# batt.net
KiCad netlist of a schematic drawn in EAGLE
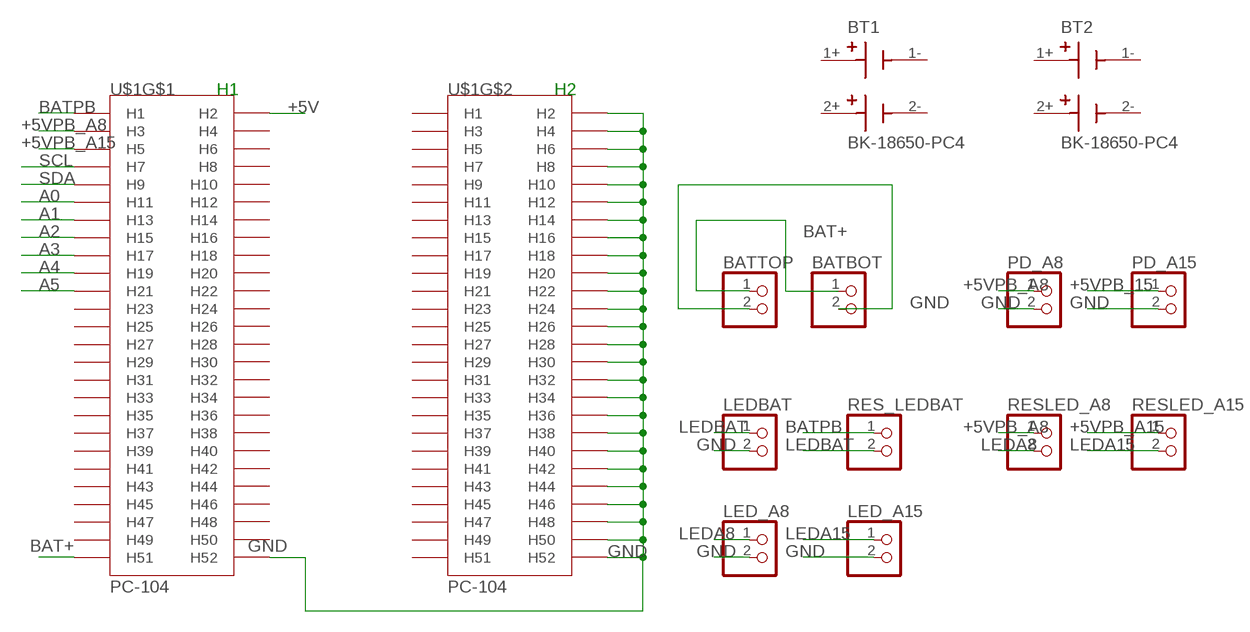
[diagram p0: schematic, sheet 1]

(export (version "E")
  (design (tool "Eeschema 10.0.6"))
  (components
    (comp (ref "BATBOT")
      (value "PINHD-1X2")
      (footprint "eagle-import:1X02")
      (libsource (lib "eagle-import") (part "PINHD-1X2"))
    )
    (comp (ref "BATTOP")
      (value "PINHD-1X2")
      (footprint "eagle-import:1X02")
      (libsource (lib "eagle-import") (part "PINHD-1X2"))
    )
    (comp (ref "BT1")
      (value "BK-18650-PC4")
      (footprint "eagle-import:BAT_BK-18650-PC4")
      (fields (field (name "MF") "MPD"))
      (libsource (lib "eagle-import") (part "BK-18650-PC4"))
    )
    (comp (ref "BT2")
      (value "BK-18650-PC4")
      (footprint "eagle-import:BAT_BK-18650-PC4")
      (fields (field (name "MF") "MPD"))
      (libsource (lib "eagle-import") (part "BK-18650-PC4"))
    )
    (comp (ref "LEDBAT")
      (value "PINHD-1X2")
      (footprint "eagle-import:1X02")
      (libsource (lib "eagle-import") (part "PINHD-1X2"))
    )
    (comp (ref "LED_A8")
      (value "PINHD-1X2")
      (footprint "eagle-import:1X02")
      (libsource (lib "eagle-import") (part "PINHD-1X2"))
    )
    (comp (ref "LED_A15")
      (value "PINHD-1X2")
      (footprint "eagle-import:1X02")
      (libsource (lib "eagle-import") (part "PINHD-1X2"))
    )
    (comp (ref "PD_A8")
      (value "PINHD-1X2")
      (footprint "eagle-import:1X02")
      (libsource (lib "eagle-import") (part "PINHD-1X2"))
    )
    (comp (ref "PD_A15")
      (value "PINHD-1X2")
      (footprint "eagle-import:1X02")
      (libsource (lib "eagle-import") (part "PINHD-1X2"))
    )
    (comp (ref "RESLED_A8")
      (value "PINHD-1X2")
      (footprint "eagle-import:1X02")
      (libsource (lib "eagle-import") (part "PINHD-1X2"))
    )
    (comp (ref "RESLED_A15")
      (value "PINHD-1X2")
      (footprint "eagle-import:1X02")
      (libsource (lib "eagle-import") (part "PINHD-1X2"))
    )
    (comp (ref "RES_LEDBAT")
      (value "PINHD-1X2")
      (footprint "eagle-import:1X02")
      (libsource (lib "eagle-import") (part "PINHD-1X2"))
    )
    (comp (ref "U$1")
      (value "PC-104")
      (footprint "eagle-import:PC-104")
      (libsource (lib "eagle-import") (part "PC-104"))
    )
  )
  (nets
    (net (code "1") (name "/+5V") (class "Default")
      (node (ref "U$1") (pin "P$2") (pinfunction "H2_P$2") (pintype "bidirectional"))
    )
    (net (code "2") (name "/+5VPB_15") (class "Default")
      (node (ref "PD_A15") (pin "1") (pinfunction "1_1") (pintype "passive"))
    )
    (net (code "3") (name "/+5VPB_A8") (class "Default")
      (node (ref "PD_A8") (pin "1") (pinfunction "1_1") (pintype "passive"))
      (node (ref "RESLED_A8") (pin "1") (pinfunction "1_1") (pintype "passive"))
      (node (ref "U$1") (pin "P$3") (pinfunction "H3_P$3") (pintype "bidirectional"))
    )
    (net (code "4") (name "/+5VPB_A15") (class "Default")
      (node (ref "RESLED_A15") (pin "1") (pinfunction "1_1") (pintype "passive"))
      (node (ref "U$1") (pin "P$5") (pinfunction "H5_P$5") (pintype "bidirectional"))
    )
    (net (code "5") (name "/A0") (class "Default")
      (node (ref "U$1") (pin "P$11") (pinfunction "H11_P$11") (pintype "bidirectional"))
    )
    (net (code "6") (name "/A1") (class "Default")
      (node (ref "U$1") (pin "P$13") (pinfunction "H13_P$13") (pintype "bidirectional"))
    )
    (net (code "7") (name "/A2") (class "Default")
      (node (ref "U$1") (pin "P$15") (pinfunction "H15_P$15") (pintype "bidirectional"))
    )
    (net (code "8") (name "/A3") (class "Default")
      (node (ref "U$1") (pin "P$17") (pinfunction "H17_P$17") (pintype "bidirectional"))
    )
    (net (code "9") (name "/A4") (class "Default")
      (node (ref "U$1") (pin "P$19") (pinfunction "H19_P$19") (pintype "bidirectional"))
    )
    (net (code "10") (name "/A5") (class "Default")
      (node (ref "U$1") (pin "P$21") (pinfunction "H21_P$21") (pintype "bidirectional"))
    )
    (net (code "11") (name "/BAT+") (class "Default")
      (node (ref "BATBOT") (pin "1") (pinfunction "1_1") (pintype "passive"))
      (node (ref "BATTOP") (pin "1") (pinfunction "1_1") (pintype "passive"))
      (node (ref "U$1") (pin "P$51") (pinfunction "H51_P$51") (pintype "bidirectional"))
    )
    (net (code "12") (name "/BATPB") (class "Default")
      (node (ref "RES_LEDBAT") (pin "1") (pinfunction "1_1") (pintype "passive"))
      (node (ref "U$1") (pin "P$1") (pinfunction "H1_P$1") (pintype "bidirectional"))
    )
    (net (code "13") (name "/GND") (class "Default")
      (node (ref "BATBOT") (pin "2") (pinfunction "2_2") (pintype "passive"))
      (node (ref "BATTOP") (pin "2") (pinfunction "2_2") (pintype "passive"))
      (node (ref "LEDBAT") (pin "2") (pinfunction "2_2") (pintype "passive"))
      (node (ref "LED_A15") (pin "2") (pinfunction "2_2") (pintype "passive"))
      (node (ref "LED_A8") (pin "2") (pinfunction "2_2") (pintype "passive"))
      (node (ref "PD_A15") (pin "2") (pinfunction "2_2") (pintype "passive"))
      (node (ref "PD_A8") (pin "2") (pinfunction "2_2") (pintype "passive"))
      (node (ref "U$1") (pin "P$100") (pinfunction "H48_P$100") (pintype "bidirectional"))
      (node (ref "U$1") (pin "P$102") (pinfunction "H50_P$102") (pintype "bidirectional"))
      (node (ref "U$1") (pin "P$104") (pinfunction "H52_P$104") (pintype "bidirectional"))
      (node (ref "U$1") (pin "P$52") (pinfunction "H52_P$52") (pintype "bidirectional"))
      (node (ref "U$1") (pin "P$54") (pinfunction "H2_P$54") (pintype "bidirectional"))
      (node (ref "U$1") (pin "P$56") (pinfunction "H4_P$56") (pintype "bidirectional"))
      (node (ref "U$1") (pin "P$58") (pinfunction "H6_P$58") (pintype "bidirectional"))
      (node (ref "U$1") (pin "P$60") (pinfunction "H8_P$60") (pintype "bidirectional"))
      (node (ref "U$1") (pin "P$62") (pinfunction "H10_P$62") (pintype "bidirectional"))
      (node (ref "U$1") (pin "P$64") (pinfunction "H12_P$64") (pintype "bidirectional"))
      (node (ref "U$1") (pin "P$66") (pinfunction "H14_P$66") (pintype "bidirectional"))
      (node (ref "U$1") (pin "P$68") (pinfunction "H16_P$68") (pintype "bidirectional"))
      (node (ref "U$1") (pin "P$70") (pinfunction "H18_P$70") (pintype "bidirectional"))
      (node (ref "U$1") (pin "P$72") (pinfunction "H20_P$72") (pintype "bidirectional"))
      (node (ref "U$1") (pin "P$74") (pinfunction "H22_P$74") (pintype "bidirectional"))
      (node (ref "U$1") (pin "P$76") (pinfunction "H24_P$76") (pintype "bidirectional"))
      (node (ref "U$1") (pin "P$78") (pinfunction "H26_P$78") (pintype "bidirectional"))
      (node (ref "U$1") (pin "P$80") (pinfunction "H28_P$80") (pintype "bidirectional"))
      (node (ref "U$1") (pin "P$82") (pinfunction "H30_P$82") (pintype "bidirectional"))
      (node (ref "U$1") (pin "P$84") (pinfunction "H32_P$84") (pintype "bidirectional"))
      (node (ref "U$1") (pin "P$86") (pinfunction "H34_P$86") (pintype "bidirectional"))
      (node (ref "U$1") (pin "P$88") (pinfunction "H36_P$88") (pintype "bidirectional"))
      (node (ref "U$1") (pin "P$90") (pinfunction "H38_P$90") (pintype "bidirectional"))
      (node (ref "U$1") (pin "P$92") (pinfunction "H40_P$92") (pintype "bidirectional"))
      (node (ref "U$1") (pin "P$94") (pinfunction "H42_P$94") (pintype "bidirectional"))
      (node (ref "U$1") (pin "P$96") (pinfunction "H44_P$96") (pintype "bidirectional"))
      (node (ref "U$1") (pin "P$98") (pinfunction "H46_P$98") (pintype "bidirectional"))
    )
    (net (code "14") (name "/LEDA8") (class "Default")
      (node (ref "LED_A8") (pin "1") (pinfunction "1_1") (pintype "passive"))
      (node (ref "RESLED_A8") (pin "2") (pinfunction "2_2") (pintype "passive"))
    )
    (net (code "15") (name "/LEDA15") (class "Default")
      (node (ref "LED_A15") (pin "1") (pinfunction "1_1") (pintype "passive"))
      (node (ref "RESLED_A15") (pin "2") (pinfunction "2_2") (pintype "passive"))
    )
    (net (code "16") (name "/LEDBAT") (class "Default")
      (node (ref "LEDBAT") (pin "1") (pinfunction "1_1") (pintype "passive"))
      (node (ref "RES_LEDBAT") (pin "2") (pinfunction "2_2") (pintype "passive"))
    )
    (net (code "17") (name "/SCL") (class "Default")
      (node (ref "U$1") (pin "P$7") (pinfunction "H7_P$7") (pintype "bidirectional"))
    )
    (net (code "18") (name "/SDA") (class "Default")
      (node (ref "U$1") (pin "P$9") (pinfunction "H9_P$9") (pintype "bidirectional"))
    )
    (net (code "19") (name "unconnected-(BT1-Pad1+)") (class "Default")
      (node (ref "BT1") (pin "1+") (pinfunction "1+_1+") (pintype "passive"))
    )
    (net (code "20") (name "unconnected-(BT1-Pad1-)") (class "Default")
      (node (ref "BT1") (pin "1-") (pinfunction "1-_1-") (pintype "passive"))
    )
    (net (code "21") (name "unconnected-(BT1-Pad2+)") (class "Default")
      (node (ref "BT1") (pin "2+") (pinfunction "2+_2+") (pintype "passive"))
    )
    (net (code "22") (name "unconnected-(BT1-Pad2-)") (class "Default")
      (node (ref "BT1") (pin "2-") (pinfunction "2-_2-") (pintype "passive"))
    )
    (net (code "23") (name "unconnected-(BT2-Pad1+)") (class "Default")
      (node (ref "BT2") (pin "1+") (pinfunction "1+_1+") (pintype "passive"))
    )
    (net (code "24") (name "unconnected-(BT2-Pad1-)") (class "Default")
      (node (ref "BT2") (pin "1-") (pinfunction "1-_1-") (pintype "passive"))
    )
    (net (code "25") (name "unconnected-(BT2-Pad2+)") (class "Default")
      (node (ref "BT2") (pin "2+") (pinfunction "2+_2+") (pintype "passive"))
    )
    (net (code "26") (name "unconnected-(BT2-Pad2-)") (class "Default")
      (node (ref "BT2") (pin "2-") (pinfunction "2-_2-") (pintype "passive"))
    )
    (net (code "27") (name "unconnected-(U$1A-H4-PadP$4)") (class "Default")
      (node (ref "U$1") (pin "P$4") (pinfunction "H4_P$4") (pintype "bidirectional"))
    )
    (net (code "28") (name "unconnected-(U$1A-H6-PadP$6)") (class "Default")
      (node (ref "U$1") (pin "P$6") (pinfunction "H6_P$6") (pintype "bidirectional"))
    )
    (net (code "29") (name "unconnected-(U$1A-H8-PadP$8)") (class "Default")
      (node (ref "U$1") (pin "P$8") (pinfunction "H8_P$8") (pintype "bidirectional"))
    )
    (net (code "30") (name "unconnected-(U$1A-H10-PadP$10)") (class "Default")
      (node (ref "U$1") (pin "P$10") (pinfunction "H10_P$10") (pintype "bidirectional"))
    )
    (net (code "31") (name "unconnected-(U$1A-H12-PadP$12)") (class "Default")
      (node (ref "U$1") (pin "P$12") (pinfunction "H12_P$12") (pintype "bidirectional"))
    )
    (net (code "32") (name "unconnected-(U$1A-H14-PadP$14)") (class "Default")
      (node (ref "U$1") (pin "P$14") (pinfunction "H14_P$14") (pintype "bidirectional"))
    )
    (net (code "33") (name "unconnected-(U$1A-H16-PadP$16)") (class "Default")
      (node (ref "U$1") (pin "P$16") (pinfunction "H16_P$16") (pintype "bidirectional"))
    )
    (net (code "34") (name "unconnected-(U$1A-H18-PadP$18)") (class "Default")
      (node (ref "U$1") (pin "P$18") (pinfunction "H18_P$18") (pintype "bidirectional"))
    )
    (net (code "35") (name "unconnected-(U$1A-H20-PadP$20)") (class "Default")
      (node (ref "U$1") (pin "P$20") (pinfunction "H20_P$20") (pintype "bidirectional"))
    )
    (net (code "36") (name "unconnected-(U$1A-H22-PadP$22)") (class "Default")
      (node (ref "U$1") (pin "P$22") (pinfunction "H22_P$22") (pintype "bidirectional"))
    )
    (net (code "37") (name "unconnected-(U$1A-H23-PadP$23)") (class "Default")
      (node (ref "U$1") (pin "P$23") (pinfunction "H23_P$23") (pintype "bidirectional"))
    )
    (net (code "38") (name "unconnected-(U$1A-H24-PadP$24)") (class "Default")
      (node (ref "U$1") (pin "P$24") (pinfunction "H24_P$24") (pintype "bidirectional"))
    )
    (net (code "39") (name "unconnected-(U$1A-H25-PadP$25)") (class "Default")
      (node (ref "U$1") (pin "P$25") (pinfunction "H25_P$25") (pintype "bidirectional"))
    )
    (net (code "40") (name "unconnected-(U$1A-H26-PadP$26)") (class "Default")
      (node (ref "U$1") (pin "P$26") (pinfunction "H26_P$26") (pintype "bidirectional"))
    )
    (net (code "41") (name "unconnected-(U$1A-H27-PadP$27)") (class "Default")
      (node (ref "U$1") (pin "P$27") (pinfunction "H27_P$27") (pintype "bidirectional"))
    )
    (net (code "42") (name "unconnected-(U$1A-H28-PadP$28)") (class "Default")
      (node (ref "U$1") (pin "P$28") (pinfunction "H28_P$28") (pintype "bidirectional"))
    )
    (net (code "43") (name "unconnected-(U$1A-H29-PadP$29)") (class "Default")
      (node (ref "U$1") (pin "P$29") (pinfunction "H29_P$29") (pintype "bidirectional"))
    )
    (net (code "44") (name "unconnected-(U$1A-H30-PadP$30)") (class "Default")
      (node (ref "U$1") (pin "P$30") (pinfunction "H30_P$30") (pintype "bidirectional"))
    )
    (net (code "45") (name "unconnected-(U$1A-H31-PadP$31)") (class "Default")
      (node (ref "U$1") (pin "P$31") (pinfunction "H31_P$31") (pintype "bidirectional"))
    )
    (net (code "46") (name "unconnected-(U$1A-H32-PadP$32)") (class "Default")
      (node (ref "U$1") (pin "P$32") (pinfunction "H32_P$32") (pintype "bidirectional"))
    )
    (net (code "47") (name "unconnected-(U$1A-H33-PadP$33)") (class "Default")
      (node (ref "U$1") (pin "P$33") (pinfunction "H33_P$33") (pintype "bidirectional"))
    )
    (net (code "48") (name "unconnected-(U$1A-H34-PadP$34)") (class "Default")
      (node (ref "U$1") (pin "P$34") (pinfunction "H34_P$34") (pintype "bidirectional"))
    )
    (net (code "49") (name "unconnected-(U$1A-H35-PadP$35)") (class "Default")
      (node (ref "U$1") (pin "P$35") (pinfunction "H35_P$35") (pintype "bidirectional"))
    )
    (net (code "50") (name "unconnected-(U$1A-H36-PadP$36)") (class "Default")
      (node (ref "U$1") (pin "P$36") (pinfunction "H36_P$36") (pintype "bidirectional"))
    )
    (net (code "51") (name "unconnected-(U$1A-H37-PadP$37)") (class "Default")
      (node (ref "U$1") (pin "P$37") (pinfunction "H37_P$37") (pintype "bidirectional"))
    )
    (net (code "52") (name "unconnected-(U$1A-H38-PadP$38)") (class "Default")
      (node (ref "U$1") (pin "P$38") (pinfunction "H38_P$38") (pintype "bidirectional"))
    )
    (net (code "53") (name "unconnected-(U$1A-H39-PadP$39)") (class "Default")
      (node (ref "U$1") (pin "P$39") (pinfunction "H39_P$39") (pintype "bidirectional"))
    )
    (net (code "54") (name "unconnected-(U$1A-H40-PadP$40)") (class "Default")
      (node (ref "U$1") (pin "P$40") (pinfunction "H40_P$40") (pintype "bidirectional"))
    )
    (net (code "55") (name "unconnected-(U$1A-H41-PadP$41)") (class "Default")
      (node (ref "U$1") (pin "P$41") (pinfunction "H41_P$41") (pintype "bidirectional"))
    )
    (net (code "56") (name "unconnected-(U$1A-H42-PadP$42)") (class "Default")
      (node (ref "U$1") (pin "P$42") (pinfunction "H42_P$42") (pintype "bidirectional"))
    )
    (net (code "57") (name "unconnected-(U$1A-H43-PadP$43)") (class "Default")
      (node (ref "U$1") (pin "P$43") (pinfunction "H43_P$43") (pintype "bidirectional"))
    )
    (net (code "58") (name "unconnected-(U$1A-H44-PadP$44)") (class "Default")
      (node (ref "U$1") (pin "P$44") (pinfunction "H44_P$44") (pintype "bidirectional"))
    )
    (net (code "59") (name "unconnected-(U$1A-H45-PadP$45)") (class "Default")
      (node (ref "U$1") (pin "P$45") (pinfunction "H45_P$45") (pintype "bidirectional"))
    )
    (net (code "60") (name "unconnected-(U$1A-H46-PadP$46)") (class "Default")
      (node (ref "U$1") (pin "P$46") (pinfunction "H46_P$46") (pintype "bidirectional"))
    )
    (net (code "61") (name "unconnected-(U$1A-H47-PadP$47)") (class "Default")
      (node (ref "U$1") (pin "P$47") (pinfunction "H47_P$47") (pintype "bidirectional"))
    )
    (net (code "62") (name "unconnected-(U$1A-H48-PadP$48)") (class "Default")
      (node (ref "U$1") (pin "P$48") (pinfunction "H48_P$48") (pintype "bidirectional"))
    )
    (net (code "63") (name "unconnected-(U$1A-H49-PadP$49)") (class "Default")
      (node (ref "U$1") (pin "P$49") (pinfunction "H49_P$49") (pintype "bidirectional"))
    )
    (net (code "64") (name "unconnected-(U$1A-H50-PadP$50)") (class "Default")
      (node (ref "U$1") (pin "P$50") (pinfunction "H50_P$50") (pintype "bidirectional"))
    )
    (net (code "65") (name "unconnected-(U$1B-H1-PadP$53)") (class "Default")
      (node (ref "U$1") (pin "P$53") (pinfunction "H1_P$53") (pintype "bidirectional"))
    )
    (net (code "66") (name "unconnected-(U$1B-H3-PadP$55)") (class "Default")
      (node (ref "U$1") (pin "P$55") (pinfunction "H3_P$55") (pintype "bidirectional"))
    )
    (net (code "67") (name "unconnected-(U$1B-H5-PadP$57)") (class "Default")
      (node (ref "U$1") (pin "P$57") (pinfunction "H5_P$57") (pintype "bidirectional"))
    )
    (net (code "68") (name "unconnected-(U$1B-H7-PadP$59)") (class "Default")
      (node (ref "U$1") (pin "P$59") (pinfunction "H7_P$59") (pintype "bidirectional"))
    )
    (net (code "69") (name "unconnected-(U$1B-H9-PadP$61)") (class "Default")
      (node (ref "U$1") (pin "P$61") (pinfunction "H9_P$61") (pintype "bidirectional"))
    )
    (net (code "70") (name "unconnected-(U$1B-H11-PadP$63)") (class "Default")
      (node (ref "U$1") (pin "P$63") (pinfunction "H11_P$63") (pintype "bidirectional"))
    )
    (net (code "71") (name "unconnected-(U$1B-H13-PadP$65)") (class "Default")
      (node (ref "U$1") (pin "P$65") (pinfunction "H13_P$65") (pintype "bidirectional"))
    )
    (net (code "72") (name "unconnected-(U$1B-H15-PadP$67)") (class "Default")
      (node (ref "U$1") (pin "P$67") (pinfunction "H15_P$67") (pintype "bidirectional"))
    )
    (net (code "73") (name "unconnected-(U$1B-H17-PadP$69)") (class "Default")
      (node (ref "U$1") (pin "P$69") (pinfunction "H17_P$69") (pintype "bidirectional"))
    )
    (net (code "74") (name "unconnected-(U$1B-H19-PadP$71)") (class "Default")
      (node (ref "U$1") (pin "P$71") (pinfunction "H19_P$71") (pintype "bidirectional"))
    )
    (net (code "75") (name "unconnected-(U$1B-H21-PadP$73)") (class "Default")
      (node (ref "U$1") (pin "P$73") (pinfunction "H21_P$73") (pintype "bidirectional"))
    )
    (net (code "76") (name "unconnected-(U$1B-H23-PadP$75)") (class "Default")
      (node (ref "U$1") (pin "P$75") (pinfunction "H23_P$75") (pintype "bidirectional"))
    )
    (net (code "77") (name "unconnected-(U$1B-H25-PadP$77)") (class "Default")
      (node (ref "U$1") (pin "P$77") (pinfunction "H25_P$77") (pintype "bidirectional"))
    )
    (net (code "78") (name "unconnected-(U$1B-H27-PadP$79)") (class "Default")
      (node (ref "U$1") (pin "P$79") (pinfunction "H27_P$79") (pintype "bidirectional"))
    )
    (net (code "79") (name "unconnected-(U$1B-H29-PadP$81)") (class "Default")
      (node (ref "U$1") (pin "P$81") (pinfunction "H29_P$81") (pintype "bidirectional"))
    )
    (net (code "80") (name "unconnected-(U$1B-H31-PadP$83)") (class "Default")
      (node (ref "U$1") (pin "P$83") (pinfunction "H31_P$83") (pintype "bidirectional"))
    )
    (net (code "81") (name "unconnected-(U$1B-H33-PadP$85)") (class "Default")
      (node (ref "U$1") (pin "P$85") (pinfunction "H33_P$85") (pintype "bidirectional"))
    )
    (net (code "82") (name "unconnected-(U$1B-H35-PadP$87)") (class "Default")
      (node (ref "U$1") (pin "P$87") (pinfunction "H35_P$87") (pintype "bidirectional"))
    )
    (net (code "83") (name "unconnected-(U$1B-H37-PadP$89)") (class "Default")
      (node (ref "U$1") (pin "P$89") (pinfunction "H37_P$89") (pintype "bidirectional"))
    )
    (net (code "84") (name "unconnected-(U$1B-H39-PadP$91)") (class "Default")
      (node (ref "U$1") (pin "P$91") (pinfunction "H39_P$91") (pintype "bidirectional"))
    )
    (net (code "85") (name "unconnected-(U$1B-H41-PadP$93)") (class "Default")
      (node (ref "U$1") (pin "P$93") (pinfunction "H41_P$93") (pintype "bidirectional"))
    )
    (net (code "86") (name "unconnected-(U$1B-H43-PadP$95)") (class "Default")
      (node (ref "U$1") (pin "P$95") (pinfunction "H43_P$95") (pintype "bidirectional"))
    )
    (net (code "87") (name "unconnected-(U$1B-H45-PadP$97)") (class "Default")
      (node (ref "U$1") (pin "P$97") (pinfunction "H45_P$97") (pintype "bidirectional"))
    )
    (net (code "88") (name "unconnected-(U$1B-H47-PadP$99)") (class "Default")
      (node (ref "U$1") (pin "P$99") (pinfunction "H47_P$99") (pintype "bidirectional"))
    )
    (net (code "89") (name "unconnected-(U$1B-H49-PadP$101)") (class "Default")
      (node (ref "U$1") (pin "P$101") (pinfunction "H49_P$101") (pintype "bidirectional"))
    )
    (net (code "90") (name "unconnected-(U$1B-H51-PadP$103)") (class "Default")
      (node (ref "U$1") (pin "P$103") (pinfunction "H51_P$103") (pintype "bidirectional"))
    )
  )
)
